# DarlekDistro.net
KiCad netlist of a schematic drawn in EAGLE
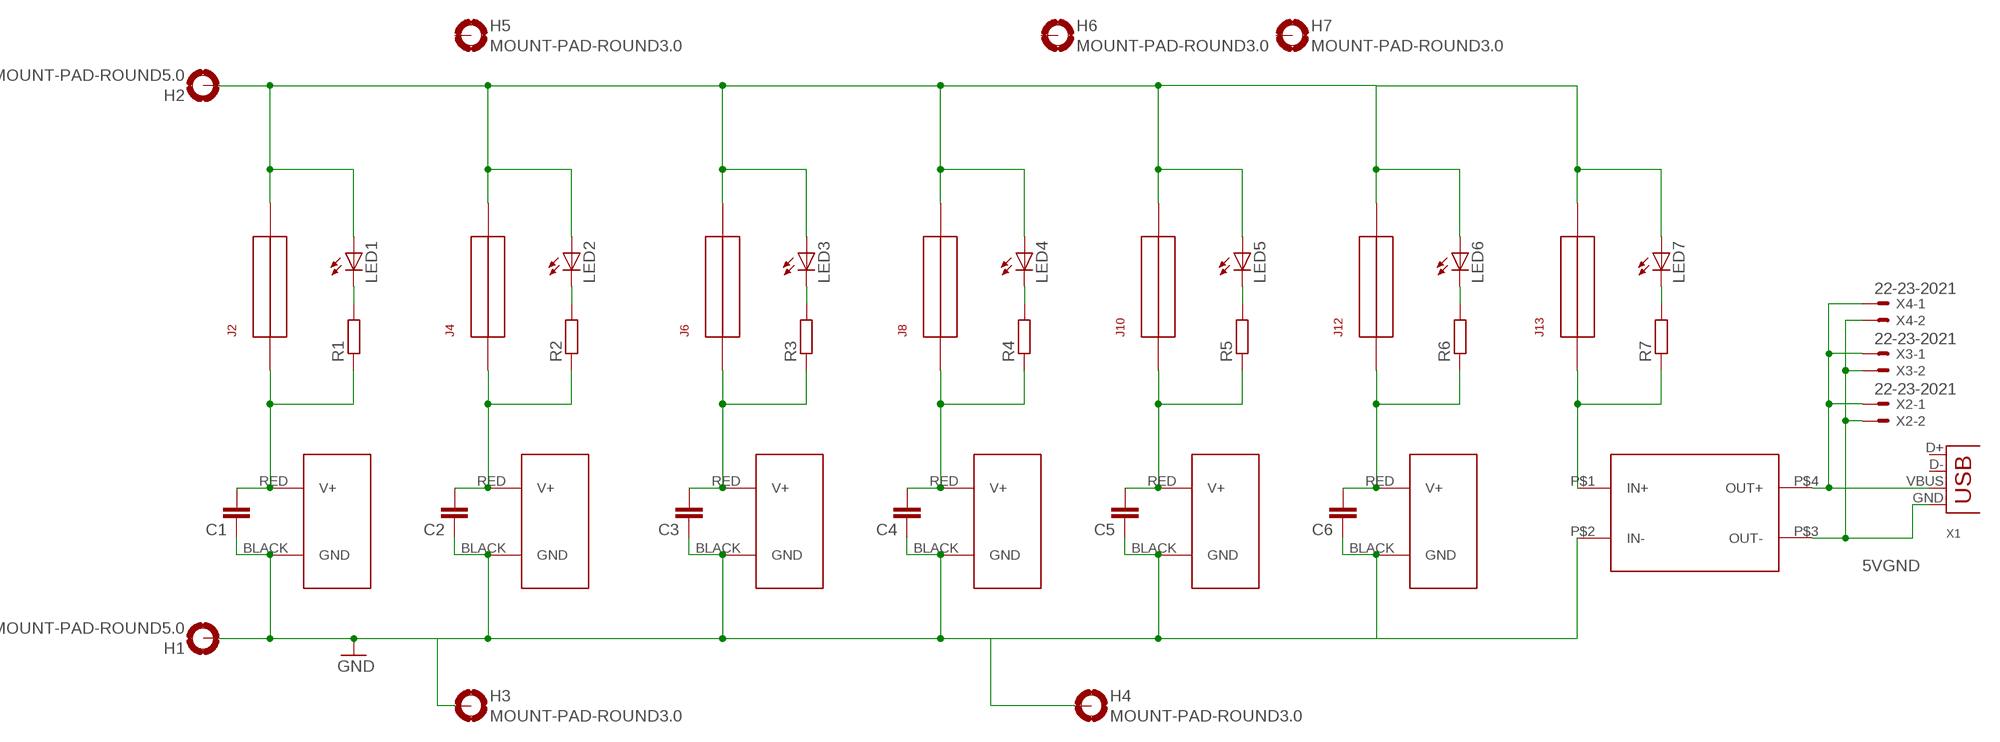
[diagram p0: schematic, sheet 1]

(export (version "E")
  (design (tool "Eeschema 10.0.6"))
  (components
    (comp (ref "C1")
      (value "C-EU050-025X075")
      (footprint "eagle-import:C050-025X075")
      (libsource (lib "eagle-import") (part "C-EU050-025X075"))
    )
    (comp (ref "C2")
      (value "C-EU050-025X075")
      (footprint "eagle-import:C050-025X075")
      (libsource (lib "eagle-import") (part "C-EU050-025X075"))
    )
    (comp (ref "C3")
      (value "C-EU050-025X075")
      (footprint "eagle-import:C050-025X075")
      (libsource (lib "eagle-import") (part "C-EU050-025X075"))
    )
    (comp (ref "C4")
      (value "C-EU050-025X075")
      (footprint "eagle-import:C050-025X075")
      (libsource (lib "eagle-import") (part "C-EU050-025X075"))
    )
    (comp (ref "C5")
      (value "C-EU050-025X075")
      (footprint "eagle-import:C050-025X075")
      (libsource (lib "eagle-import") (part "C-EU050-025X075"))
    )
    (comp (ref "C6")
      (value "C-EU050-025X075")
      (footprint "eagle-import:C050-025X075")
      (libsource (lib "eagle-import") (part "C-EU050-025X075"))
    )
    (comp (ref "H1")
      (value "MOUNT-PAD-ROUND5.0")
      (footprint "eagle-import:5,0-PAD")
      (libsource (lib "eagle-import") (part "MOUNT-PAD-ROUND5.0"))
    )
    (comp (ref "H2")
      (value "MOUNT-PAD-ROUND5.0")
      (footprint "eagle-import:5,0-PAD")
      (libsource (lib "eagle-import") (part "MOUNT-PAD-ROUND5.0"))
    )
    (comp (ref "H3")
      (value "MOUNT-PAD-ROUND3.0")
      (footprint "eagle-import:3,0-PAD")
      (libsource (lib "eagle-import") (part "MOUNT-PAD-ROUND3.0"))
    )
    (comp (ref "H4")
      (value "MOUNT-PAD-ROUND3.0")
      (footprint "eagle-import:3,0-PAD")
      (libsource (lib "eagle-import") (part "MOUNT-PAD-ROUND3.0"))
    )
    (comp (ref "H5")
      (value "MOUNT-PAD-ROUND3.0")
      (footprint "eagle-import:3,0-PAD")
      (libsource (lib "eagle-import") (part "MOUNT-PAD-ROUND3.0"))
    )
    (comp (ref "H6")
      (value "MOUNT-PAD-ROUND3.0")
      (footprint "eagle-import:3,0-PAD")
      (libsource (lib "eagle-import") (part "MOUNT-PAD-ROUND3.0"))
    )
    (comp (ref "H7")
      (value "MOUNT-PAD-ROUND3.0")
      (footprint "eagle-import:3,0-PAD")
      (libsource (lib "eagle-import") (part "MOUNT-PAD-ROUND3.0"))
    )
    (comp (ref "J1")
      (value "POWERPOLE_POWER10AWG")
      (footprint "eagle-import:POWERPOLE_PAIR_10AWG")
      (libsource (lib "eagle-import") (part "POWERPOLE_POWER10AWG"))
    )
    (comp (ref "J2")
      (value "FUSEATC")
      (footprint "eagle-import:FUSE_ATC")
      (libsource (lib "eagle-import") (part "FUSEATC"))
    )
    (comp (ref "J3")
      (value "POWERPOLE_POWER10AWG")
      (footprint "eagle-import:POWERPOLE_PAIR_10AWG")
      (libsource (lib "eagle-import") (part "POWERPOLE_POWER10AWG"))
    )
    (comp (ref "J4")
      (value "FUSEATC")
      (footprint "eagle-import:FUSE_ATC")
      (libsource (lib "eagle-import") (part "FUSEATC"))
    )
    (comp (ref "J5")
      (value "POWERPOLE_POWER10AWG")
      (footprint "eagle-import:POWERPOLE_PAIR_10AWG")
      (libsource (lib "eagle-import") (part "POWERPOLE_POWER10AWG"))
    )
    (comp (ref "J6")
      (value "FUSEATC")
      (footprint "eagle-import:FUSE_ATC")
      (libsource (lib "eagle-import") (part "FUSEATC"))
    )
    (comp (ref "J7")
      (value "POWERPOLE_POWER10AWG")
      (footprint "eagle-import:POWERPOLE_PAIR_10AWG")
      (libsource (lib "eagle-import") (part "POWERPOLE_POWER10AWG"))
    )
    (comp (ref "J8")
      (value "FUSEATC")
      (footprint "eagle-import:FUSE_ATC")
      (libsource (lib "eagle-import") (part "FUSEATC"))
    )
    (comp (ref "J9")
      (value "POWERPOLE_POWER10AWG")
      (footprint "eagle-import:POWERPOLE_PAIR_10AWG")
      (libsource (lib "eagle-import") (part "POWERPOLE_POWER10AWG"))
    )
    (comp (ref "J10")
      (value "FUSEATC")
      (footprint "eagle-import:FUSE_ATC")
      (libsource (lib "eagle-import") (part "FUSEATC"))
    )
    (comp (ref "J11")
      (value "POWERPOLE_POWER10AWG")
      (footprint "eagle-import:POWERPOLE_PAIR_10AWG")
      (libsource (lib "eagle-import") (part "POWERPOLE_POWER10AWG"))
    )
    (comp (ref "J12")
      (value "FUSEATC")
      (footprint "eagle-import:FUSE_ATC")
      (libsource (lib "eagle-import") (part "FUSEATC"))
    )
    (comp (ref "J13")
      (value "FUSEATC")
      (footprint "eagle-import:FUSE_ATC")
      (libsource (lib "eagle-import") (part "FUSEATC"))
    )
    (comp (ref "LED1")
      (value "LED3MM")
      (footprint "eagle-import:LED3MM")
      (libsource (lib "eagle-import") (part "LED3MM"))
    )
    (comp (ref "LED2")
      (value "LED3MM")
      (footprint "eagle-import:LED3MM")
      (libsource (lib "eagle-import") (part "LED3MM"))
    )
    (comp (ref "LED3")
      (value "LED3MM")
      (footprint "eagle-import:LED3MM")
      (libsource (lib "eagle-import") (part "LED3MM"))
    )
    (comp (ref "LED4")
      (value "LED3MM")
      (footprint "eagle-import:LED3MM")
      (libsource (lib "eagle-import") (part "LED3MM"))
    )
    (comp (ref "LED5")
      (value "LED3MM")
      (footprint "eagle-import:LED3MM")
      (libsource (lib "eagle-import") (part "LED3MM"))
    )
    (comp (ref "LED6")
      (value "LED3MM")
      (footprint "eagle-import:LED3MM")
      (libsource (lib "eagle-import") (part "LED3MM"))
    )
    (comp (ref "LED7")
      (value "LED3MM")
      (footprint "eagle-import:LED3MM")
      (libsource (lib "eagle-import") (part "LED3MM"))
    )
    (comp (ref "R1")
      (value "R-EU_0204/7")
      (footprint "eagle-import:0204_7")
      (libsource (lib "eagle-import") (part "R-EU_0204/7"))
    )
    (comp (ref "R2")
      (value "R-EU_0204/7")
      (footprint "eagle-import:0204_7")
      (libsource (lib "eagle-import") (part "R-EU_0204/7"))
    )
    (comp (ref "R3")
      (value "R-EU_0204/7")
      (footprint "eagle-import:0204_7")
      (libsource (lib "eagle-import") (part "R-EU_0204/7"))
    )
    (comp (ref "R4")
      (value "R-EU_0204/7")
      (footprint "eagle-import:0204_7")
      (libsource (lib "eagle-import") (part "R-EU_0204/7"))
    )
    (comp (ref "R5")
      (value "R-EU_0204/7")
      (footprint "eagle-import:0204_7")
      (libsource (lib "eagle-import") (part "R-EU_0204/7"))
    )
    (comp (ref "R6")
      (value "R-EU_0204/7")
      (footprint "eagle-import:0204_7")
      (libsource (lib "eagle-import") (part "R-EU_0204/7"))
    )
    (comp (ref "R7")
      (value "R-EU_0204/7")
      (footprint "eagle-import:0204_7")
      (libsource (lib "eagle-import") (part "R-EU_0204/7"))
    )
    (comp (ref "U$1")
      (value "DSN2596_REG")
      (footprint "eagle-import:DSN2596_REG")
      (libsource (lib "eagle-import") (part "DSN2596_REG"))
    )
    (comp (ref "X1")
      (value "USB-A-H")
      (footprint "eagle-import:USB-A-H")
      (libsource (lib "eagle-import") (part "USB-A-H"))
    )
    (comp (ref "X2")
      (value "22-23-2021")
      (footprint "eagle-import:22-23-2021")
      (fields (field (name "MF") "MOLEX"))
      (libsource (lib "eagle-import") (part "22-23-2021"))
    )
    (comp (ref "X3")
      (value "22-23-2021")
      (footprint "eagle-import:22-23-2021")
      (fields (field (name "MF") "MOLEX"))
      (libsource (lib "eagle-import") (part "22-23-2021"))
    )
    (comp (ref "X4")
      (value "22-23-2021")
      (footprint "eagle-import:22-23-2021")
      (fields (field (name "MF") "MOLEX"))
      (libsource (lib "eagle-import") (part "22-23-2021"))
    )
  )
  (nets
    (net (code "1") (name "/5VGND") (class "Default")
      (node (ref "U$1") (pin "P$3") (pinfunction "OUT-_P$3") (pintype "bidirectional"))
      (node (ref "X1") (pin "GND") (pinfunction "GND_GND") (pintype "bidirectional"))
      (node (ref "X2") (pin "2") (pinfunction "S_2") (pintype "passive"))
      (node (ref "X3") (pin "2") (pinfunction "S_2") (pintype "passive"))
      (node (ref "X4") (pin "2") (pinfunction "S_2") (pintype "passive"))
    )
    (net (code "2") (name "GND") (class "Default")
      (node (ref "C1") (pin "1") (pinfunction "1_1") (pintype "passive"))
      (node (ref "C2") (pin "1") (pinfunction "1_1") (pintype "passive"))
      (node (ref "C3") (pin "1") (pinfunction "1_1") (pintype "passive"))
      (node (ref "C4") (pin "1") (pinfunction "1_1") (pintype "passive"))
      (node (ref "C5") (pin "1") (pinfunction "1_1") (pintype "passive"))
      (node (ref "C6") (pin "1") (pinfunction "1_1") (pintype "passive"))
      (node (ref "H1") (pin "B5") (pinfunction "MOUNT_B5") (pintype "passive"))
      (node (ref "H3") (pin "B3,0") (pinfunction "MOUNT_B3,0") (pintype "passive"))
      (node (ref "H4") (pin "B3,0") (pinfunction "MOUNT_B3,0") (pintype "passive"))
      (node (ref "J1") (pin "BLACK") (pinfunction "GND_BLACK") (pintype "power_in"))
      (node (ref "J11") (pin "BLACK") (pinfunction "GND_BLACK") (pintype "power_in"))
      (node (ref "J3") (pin "BLACK") (pinfunction "GND_BLACK") (pintype "power_in"))
      (node (ref "J5") (pin "BLACK") (pinfunction "GND_BLACK") (pintype "power_in"))
      (node (ref "J7") (pin "BLACK") (pinfunction "GND_BLACK") (pintype "power_in"))
      (node (ref "J9") (pin "BLACK") (pinfunction "GND_BLACK") (pintype "power_in"))
      (node (ref "U$1") (pin "P$2") (pinfunction "IN-_P$2") (pintype "bidirectional"))
    )
    (net (code "3") (name "Net-(H2-MOUNT)") (class "Default")
      (node (ref "H2") (pin "B5") (pinfunction "MOUNT_B5") (pintype "passive"))
      (node (ref "J10") (pin "P$3") (pinfunction "P$2_P$3") (pintype "bidirectional"))
      (node (ref "J10") (pin "P$4") (pinfunction "P$2_P$4") (pintype "bidirectional"))
      (node (ref "J12") (pin "P$3") (pinfunction "P$2_P$3") (pintype "bidirectional"))
      (node (ref "J12") (pin "P$4") (pinfunction "P$2_P$4") (pintype "bidirectional"))
      (node (ref "J13") (pin "P$3") (pinfunction "P$2_P$3") (pintype "bidirectional"))
      (node (ref "J13") (pin "P$4") (pinfunction "P$2_P$4") (pintype "bidirectional"))
      (node (ref "J2") (pin "P$3") (pinfunction "P$2_P$3") (pintype "bidirectional"))
      (node (ref "J2") (pin "P$4") (pinfunction "P$2_P$4") (pintype "bidirectional"))
      (node (ref "J4") (pin "P$3") (pinfunction "P$2_P$3") (pintype "bidirectional"))
      (node (ref "J4") (pin "P$4") (pinfunction "P$2_P$4") (pintype "bidirectional"))
      (node (ref "J6") (pin "P$3") (pinfunction "P$2_P$3") (pintype "bidirectional"))
      (node (ref "J6") (pin "P$4") (pinfunction "P$2_P$4") (pintype "bidirectional"))
      (node (ref "J8") (pin "P$3") (pinfunction "P$2_P$3") (pintype "bidirectional"))
      (node (ref "J8") (pin "P$4") (pinfunction "P$2_P$4") (pintype "bidirectional"))
      (node (ref "LED1") (pin "A") (pinfunction "A_A") (pintype "passive"))
      (node (ref "LED2") (pin "A") (pinfunction "A_A") (pintype "passive"))
      (node (ref "LED3") (pin "A") (pinfunction "A_A") (pintype "passive"))
      (node (ref "LED4") (pin "A") (pinfunction "A_A") (pintype "passive"))
      (node (ref "LED5") (pin "A") (pinfunction "A_A") (pintype "passive"))
      (node (ref "LED6") (pin "A") (pinfunction "A_A") (pintype "passive"))
      (node (ref "LED7") (pin "A") (pinfunction "A_A") (pintype "passive"))
    )
    (net (code "4") (name "Net-(J1-V+)") (class "Default")
      (node (ref "C1") (pin "2") (pinfunction "2_2") (pintype "passive"))
      (node (ref "J1") (pin "RED") (pinfunction "V+_RED") (pintype "power_in"))
      (node (ref "J2") (pin "P$1") (pinfunction "P$1_P$1") (pintype "bidirectional"))
      (node (ref "J2") (pin "P$2") (pinfunction "P$1_P$2") (pintype "bidirectional"))
      (node (ref "R1") (pin "1") (pinfunction "1_1") (pintype "passive"))
    )
    (net (code "5") (name "Net-(J3-V+)") (class "Default")
      (node (ref "C2") (pin "2") (pinfunction "2_2") (pintype "passive"))
      (node (ref "J3") (pin "RED") (pinfunction "V+_RED") (pintype "power_in"))
      (node (ref "J4") (pin "P$1") (pinfunction "P$1_P$1") (pintype "bidirectional"))
      (node (ref "J4") (pin "P$2") (pinfunction "P$1_P$2") (pintype "bidirectional"))
      (node (ref "R2") (pin "1") (pinfunction "1_1") (pintype "passive"))
    )
    (net (code "6") (name "Net-(J5-V+)") (class "Default")
      (node (ref "C3") (pin "2") (pinfunction "2_2") (pintype "passive"))
      (node (ref "J5") (pin "RED") (pinfunction "V+_RED") (pintype "power_in"))
      (node (ref "J6") (pin "P$1") (pinfunction "P$1_P$1") (pintype "bidirectional"))
      (node (ref "J6") (pin "P$2") (pinfunction "P$1_P$2") (pintype "bidirectional"))
      (node (ref "R3") (pin "1") (pinfunction "1_1") (pintype "passive"))
    )
    (net (code "7") (name "Net-(J7-V+)") (class "Default")
      (node (ref "C4") (pin "2") (pinfunction "2_2") (pintype "passive"))
      (node (ref "J7") (pin "RED") (pinfunction "V+_RED") (pintype "power_in"))
      (node (ref "J8") (pin "P$1") (pinfunction "P$1_P$1") (pintype "bidirectional"))
      (node (ref "J8") (pin "P$2") (pinfunction "P$1_P$2") (pintype "bidirectional"))
      (node (ref "R4") (pin "1") (pinfunction "1_1") (pintype "passive"))
    )
    (net (code "8") (name "Net-(J9-V+)") (class "Default")
      (node (ref "C5") (pin "2") (pinfunction "2_2") (pintype "passive"))
      (node (ref "J10") (pin "P$1") (pinfunction "P$1_P$1") (pintype "bidirectional"))
      (node (ref "J10") (pin "P$2") (pinfunction "P$1_P$2") (pintype "bidirectional"))
      (node (ref "J9") (pin "RED") (pinfunction "V+_RED") (pintype "power_in"))
      (node (ref "R5") (pin "1") (pinfunction "1_1") (pintype "passive"))
    )
    (net (code "9") (name "Net-(J11-V+)") (class "Default")
      (node (ref "C6") (pin "2") (pinfunction "2_2") (pintype "passive"))
      (node (ref "J11") (pin "RED") (pinfunction "V+_RED") (pintype "power_in"))
      (node (ref "J12") (pin "P$1") (pinfunction "P$1_P$1") (pintype "bidirectional"))
      (node (ref "J12") (pin "P$2") (pinfunction "P$1_P$2") (pintype "bidirectional"))
      (node (ref "R6") (pin "1") (pinfunction "1_1") (pintype "passive"))
    )
    (net (code "10") (name "Net-(LED1-C)") (class "Default")
      (node (ref "LED1") (pin "K") (pinfunction "C_K") (pintype "passive"))
      (node (ref "R1") (pin "2") (pinfunction "2_2") (pintype "passive"))
    )
    (net (code "11") (name "Net-(LED2-C)") (class "Default")
      (node (ref "LED2") (pin "K") (pinfunction "C_K") (pintype "passive"))
      (node (ref "R2") (pin "2") (pinfunction "2_2") (pintype "passive"))
    )
    (net (code "12") (name "Net-(LED3-C)") (class "Default")
      (node (ref "LED3") (pin "K") (pinfunction "C_K") (pintype "passive"))
      (node (ref "R3") (pin "2") (pinfunction "2_2") (pintype "passive"))
    )
    (net (code "13") (name "Net-(LED4-C)") (class "Default")
      (node (ref "LED4") (pin "K") (pinfunction "C_K") (pintype "passive"))
      (node (ref "R4") (pin "2") (pinfunction "2_2") (pintype "passive"))
    )
    (net (code "14") (name "Net-(LED5-C)") (class "Default")
      (node (ref "LED5") (pin "K") (pinfunction "C_K") (pintype "passive"))
      (node (ref "R5") (pin "2") (pinfunction "2_2") (pintype "passive"))
    )
    (net (code "15") (name "Net-(LED6-C)") (class "Default")
      (node (ref "LED6") (pin "K") (pinfunction "C_K") (pintype "passive"))
      (node (ref "R6") (pin "2") (pinfunction "2_2") (pintype "passive"))
    )
    (net (code "16") (name "Net-(LED7-C)") (class "Default")
      (node (ref "LED7") (pin "K") (pinfunction "C_K") (pintype "passive"))
      (node (ref "R7") (pin "2") (pinfunction "2_2") (pintype "passive"))
    )
    (net (code "17") (name "Net-(U$1-IN+)") (class "Default")
      (node (ref "J13") (pin "P$1") (pinfunction "P$1_P$1") (pintype "bidirectional"))
      (node (ref "J13") (pin "P$2") (pinfunction "P$1_P$2") (pintype "bidirectional"))
      (node (ref "R7") (pin "1") (pinfunction "1_1") (pintype "passive"))
      (node (ref "U$1") (pin "P$1") (pinfunction "IN+_P$1") (pintype "bidirectional"))
    )
    (net (code "18") (name "Net-(U$1-OUT+)") (class "Default")
      (node (ref "U$1") (pin "P$4") (pinfunction "OUT+_P$4") (pintype "bidirectional"))
      (node (ref "X1") (pin "VBUS") (pinfunction "VBUS_VBUS") (pintype "bidirectional"))
      (node (ref "X2") (pin "1") (pinfunction "S_1") (pintype "passive"))
      (node (ref "X3") (pin "1") (pinfunction "S_1") (pintype "passive"))
      (node (ref "X4") (pin "1") (pinfunction "S_1") (pintype "passive"))
    )
    (net (code "19") (name "unconnected-(H5-MOUNT-PadB3,0)") (class "Default")
      (node (ref "H5") (pin "B3,0") (pinfunction "MOUNT_B3,0") (pintype "passive"))
    )
    (net (code "20") (name "unconnected-(H6-MOUNT-PadB3,0)") (class "Default")
      (node (ref "H6") (pin "B3,0") (pinfunction "MOUNT_B3,0") (pintype "passive"))
    )
    (net (code "21") (name "unconnected-(H7-MOUNT-PadB3,0)") (class "Default")
      (node (ref "H7") (pin "B3,0") (pinfunction "MOUNT_B3,0") (pintype "passive"))
    )
    (net (code "22") (name "unconnected-(X1-PadD+)") (class "Default")
      (node (ref "X1") (pin "D+") (pinfunction "D+_D+") (pintype "bidirectional"))
    )
    (net (code "23") (name "unconnected-(X1-PadD-)") (class "Default")
      (node (ref "X1") (pin "D-") (pinfunction "D-_D-") (pintype "bidirectional"))
    )
  )
)
